# Sheet1.net
KiCad netlist of a schematic drawn in Altium Designer
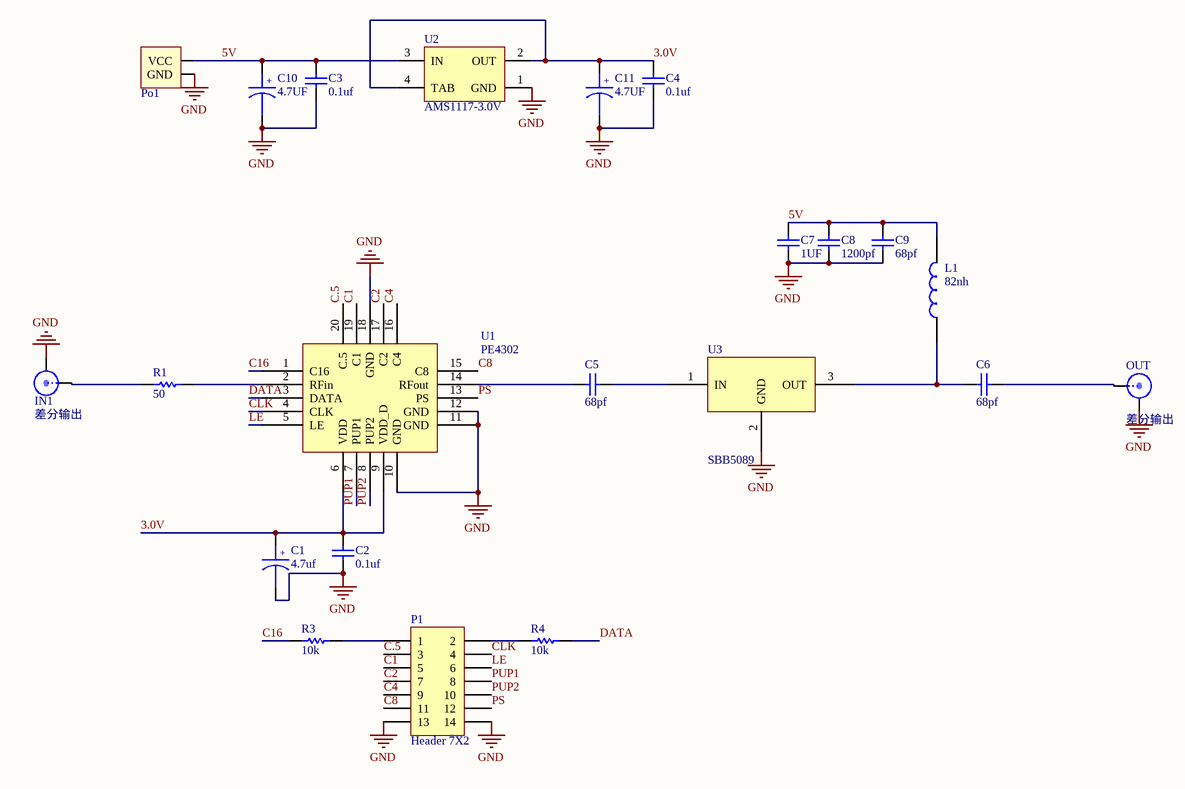
[diagram p0: Sheet1.SchDoc]

(export (version "E")
  (design (tool "Eeschema 10.0.6"))
  (components
    (comp (ref "C1")
      (value "4.7uf")
      (footprint "7343-31 TYPE D")
      (libsource (lib "Schlib1") (part "Tantalium Cap"))
    )
    (comp (ref "C2") (value "0.1uf") (footprint "0603C") (libsource (lib "Schlib1") (part "Cap")))
    (comp (ref "C3") (value "0.1uf") (footprint "0805") (libsource (lib "Schlib1") (part "Cap")))
    (comp (ref "C4") (value "0.1uf") (footprint "0805") (libsource (lib "Schlib1") (part "Cap")))
    (comp (ref "C5") (value "68pf") (footprint "0805") (libsource (lib "Schlib1") (part "Cap")))
    (comp (ref "C6") (value "68pf") (footprint "0805") (libsource (lib "Schlib1") (part "Cap")))
    (comp (ref "C7") (value "1UF") (footprint "0805") (libsource (lib "Schlib1") (part "Cap")))
    (comp (ref "C8") (value "1200pf") (footprint "0805") (libsource (lib "Schlib1") (part "Cap")))
    (comp (ref "C9") (value "68pf") (footprint "0805") (libsource (lib "Schlib1") (part "Cap")))
    (comp (ref "C10")
      (value "4.7UF")
      (footprint "7343-31 TYPE D")
      (libsource (lib "Schlib1") (part "Tantalium Cap"))
    )
    (comp (ref "C11")
      (value "4.7UF")
      (footprint "7343-31 TYPE D")
      (libsource (lib "Schlib1") (part "Tantalium Cap"))
    )
    (comp (ref "IN1") (value "差分输出") (footprint "SMA-LYING") (libsource (lib "Schlib1") (part "SMA")))
    (comp (ref "L1") (value "82nh") (footprint "0805") (libsource (lib "Schlib1") (part "Inductor")))
    (comp (ref "OUT") (value "差分输出") (footprint "SMA-LYING") (libsource (lib "Schlib1") (part "SMA")))
    (comp (ref "P1")
      (value "Header 7X2")
      (footprint "HDR2X7")
      (description "Header, 7-Pin, Dual row")
      (fields (field (name "PUBLISHER") "Altium Limited"))
      (libsource (lib "Miscellaneous Connectors") (part "Header 7X2"))
    )
    (comp (ref "Po1")
      (value "Power_2Port")
      (footprint "Power_S_2Port")
      (libsource (lib "Schlib1") (part "Power_2Port"))
    )
    (comp (ref "R1") (value "50") (footprint "0805") (libsource (lib "Schlib1") (part "Res")))
    (comp (ref "R3") (value "10k") (footprint "0603R") (libsource (lib "Schlib1") (part "Res")))
    (comp (ref "R4") (value "10k") (footprint "0603R") (libsource (lib "Schlib1") (part "Res")))
    (comp (ref "U1")
      (value "PE4302")
      (footprint "LC-QFN-20_4x4x05P")
      (libsource (lib "Schlib1") (part "PE4302"))
    )
    (comp (ref "U2")
      (value "AMS1117-3.0V")
      (footprint "SOT223")
      (libsource (lib "Schlib1") (part "AMS1117-3.0V"))
    )
    (comp (ref "U3") (value "SBB5089") (footprint "SOT-89") (libsource (lib "Schlib1") (part "SBB5089")))
  )
  (nets
    (net (code "1") (name "/3.0V") (class "Default")
      (node (ref "C1") (pin "1") (pinfunction "1_1") (pintype "passive"))
      (node (ref "C11") (pin "1") (pinfunction "1_1") (pintype "passive"))
      (node (ref "C2") (pin "2") (pinfunction "2_2") (pintype "passive"))
      (node (ref "C4") (pin "2") (pinfunction "2_2") (pintype "passive"))
      (node (ref "U1") (pin "6") (pinfunction "VDD_6") (pintype "passive"))
      (node (ref "U1") (pin "9") (pinfunction "VDD_D_9") (pintype "passive"))
      (node (ref "U2") (pin "2") (pinfunction "OUT_2") (pintype "power_in"))
      (node (ref "U2") (pin "4") (pinfunction "TAB_4") (pintype "power_in"))
    )
    (net (code "2") (name "/5V") (class "Default")
      (node (ref "C10") (pin "1") (pinfunction "1_1") (pintype "passive"))
      (node (ref "C3") (pin "2") (pinfunction "2_2") (pintype "passive"))
      (node (ref "C7") (pin "1") (pinfunction "1_1") (pintype "passive"))
      (node (ref "C8") (pin "1") (pinfunction "1_1") (pintype "passive"))
      (node (ref "C9") (pin "1") (pinfunction "1_1") (pintype "passive"))
      (node (ref "L1") (pin "2") (pintype "passive"))
      (node (ref "Po1") (pin "1") (pinfunction "VCC_1") (pintype "passive"))
      (node (ref "U2") (pin "3") (pinfunction "IN_3") (pintype "power_in"))
    )
    (net (code "3") (name "/C.5") (class "Default")
      (node (ref "P1") (pin "3") (pinfunction "3_3") (pintype "passive"))
      (node (ref "U1") (pin "20") (pinfunction "C.5_20") (pintype "passive"))
    )
    (net (code "4") (name "/C1") (class "Default")
      (node (ref "P1") (pin "5") (pinfunction "5_5") (pintype "passive"))
      (node (ref "U1") (pin "19") (pinfunction "C1_19") (pintype "passive"))
    )
    (net (code "5") (name "/C2") (class "Default")
      (node (ref "P1") (pin "7") (pinfunction "7_7") (pintype "passive"))
      (node (ref "U1") (pin "17") (pinfunction "C2_17") (pintype "passive"))
    )
    (net (code "6") (name "/C4") (class "Default")
      (node (ref "P1") (pin "9") (pinfunction "9_9") (pintype "passive"))
      (node (ref "U1") (pin "16") (pinfunction "C4_16") (pintype "passive"))
    )
    (net (code "7") (name "/C8") (class "Default")
      (node (ref "P1") (pin "11") (pinfunction "11_11") (pintype "passive"))
      (node (ref "U1") (pin "15") (pinfunction "C8_15") (pintype "passive"))
    )
    (net (code "8") (name "/C16") (class "Default")
      (node (ref "R3") (pin "1") (pinfunction "1_1") (pintype "passive"))
      (node (ref "U1") (pin "1") (pinfunction "C16_1") (pintype "passive"))
    )
    (net (code "9") (name "/CLK") (class "Default")
      (node (ref "P1") (pin "4") (pinfunction "4_4") (pintype "passive"))
      (node (ref "U1") (pin "4") (pinfunction "CLK_4") (pintype "passive"))
    )
    (net (code "10") (name "/DATA") (class "Default")
      (node (ref "R4") (pin "2") (pinfunction "2_2") (pintype "passive"))
      (node (ref "U1") (pin "3") (pinfunction "DATA_3") (pintype "passive"))
    )
    (net (code "11") (name "/LE") (class "Default")
      (node (ref "P1") (pin "6") (pinfunction "6_6") (pintype "passive"))
      (node (ref "U1") (pin "5") (pinfunction "LE_5") (pintype "passive"))
    )
    (net (code "12") (name "/PS") (class "Default")
      (node (ref "P1") (pin "12") (pinfunction "12_12") (pintype "passive"))
      (node (ref "U1") (pin "13") (pinfunction "PS_13") (pintype "passive"))
    )
    (net (code "13") (name "/PUP1") (class "Default")
      (node (ref "P1") (pin "8") (pinfunction "8_8") (pintype "passive"))
      (node (ref "U1") (pin "7") (pinfunction "PUP1_7") (pintype "passive"))
    )
    (net (code "14") (name "/PUP2") (class "Default")
      (node (ref "P1") (pin "10") (pinfunction "10_10") (pintype "passive"))
      (node (ref "U1") (pin "8") (pinfunction "PUP2_8") (pintype "passive"))
    )
    (net (code "15") (name "GND") (class "Default")
      (node (ref "C1") (pin "2") (pinfunction "2_2") (pintype "passive"))
      (node (ref "C10") (pin "2") (pinfunction "2_2") (pintype "passive"))
      (node (ref "C11") (pin "2") (pinfunction "2_2") (pintype "passive"))
      (node (ref "C2") (pin "1") (pinfunction "1_1") (pintype "passive"))
      (node (ref "C3") (pin "1") (pinfunction "1_1") (pintype "passive"))
      (node (ref "C4") (pin "1") (pinfunction "1_1") (pintype "passive"))
      (node (ref "C7") (pin "2") (pinfunction "2_2") (pintype "passive"))
      (node (ref "C8") (pin "2") (pinfunction "2_2") (pintype "passive"))
      (node (ref "C9") (pin "2") (pinfunction "2_2") (pintype "passive"))
      (node (ref "IN1") (pin "1") (pinfunction "1_1") (pintype "passive"))
      (node (ref "OUT") (pin "1") (pinfunction "1_1") (pintype "passive"))
      (node (ref "P1") (pin "13") (pinfunction "13_13") (pintype "passive"))
      (node (ref "P1") (pin "14") (pinfunction "14_14") (pintype "passive"))
      (node (ref "Po1") (pin "2") (pinfunction "GND_2") (pintype "passive"))
      (node (ref "U1") (pin "10") (pinfunction "GND_10") (pintype "passive"))
      (node (ref "U1") (pin "11") (pinfunction "GND_11") (pintype "passive"))
      (node (ref "U1") (pin "12") (pinfunction "GND_12") (pintype "passive"))
      (node (ref "U1") (pin "18") (pinfunction "GND_18") (pintype "passive"))
      (node (ref "U2") (pin "1") (pinfunction "GND_1") (pintype "power_in"))
      (node (ref "U3") (pin "2") (pinfunction "GND_2") (pintype "passive"))
    )
    (net (code "16") (name "Net-(C6-Pad1)") (class "Default")
      (node (ref "C6") (pin "1") (pinfunction "1_1") (pintype "passive"))
      (node (ref "OUT") (pin "0") (pinfunction "0_0") (pintype "passive"))
    )
    (net (code "17") (name "Net-(IN1-Pad0)") (class "Default")
      (node (ref "IN1") (pin "0") (pinfunction "0_0") (pintype "passive"))
      (node (ref "R1") (pin "1") (pinfunction "1_1") (pintype "passive"))
    )
    (net (code "18") (name "Net-(P1-Pad1)") (class "Default")
      (node (ref "P1") (pin "1") (pinfunction "1_1") (pintype "passive"))
      (node (ref "R3") (pin "2") (pinfunction "2_2") (pintype "passive"))
    )
    (net (code "19") (name "Net-(P1-Pad2)") (class "Default")
      (node (ref "P1") (pin "2") (pinfunction "2_2") (pintype "passive"))
      (node (ref "R4") (pin "1") (pinfunction "1_1") (pintype "passive"))
    )
    (net (code "20") (name "Net-(U1-RFin)") (class "Default")
      (node (ref "R1") (pin "2") (pinfunction "2_2") (pintype "passive"))
      (node (ref "U1") (pin "2") (pinfunction "RFin_2") (pintype "passive"))
    )
    (net (code "21") (name "Net-(U1-RFout)") (class "Default")
      (node (ref "C5") (pin "2") (pinfunction "2_2") (pintype "passive"))
      (node (ref "U1") (pin "14") (pinfunction "RFout_14") (pintype "passive"))
    )
    (net (code "22") (name "Net-(U3-IN)") (class "Default")
      (node (ref "C5") (pin "1") (pinfunction "1_1") (pintype "passive"))
      (node (ref "U3") (pin "1") (pinfunction "IN_1") (pintype "passive"))
    )
    (net (code "23") (name "Net-(U3-OUT)") (class "Default")
      (node (ref "C6") (pin "2") (pinfunction "2_2") (pintype "passive"))
      (node (ref "L1") (pin "1") (pintype "passive"))
      (node (ref "U3") (pin "3") (pinfunction "OUT_3") (pintype "passive"))
    )
  )
)
